# QRS_1_0.net
KiCad netlist of a schematic drawn in EAGLE
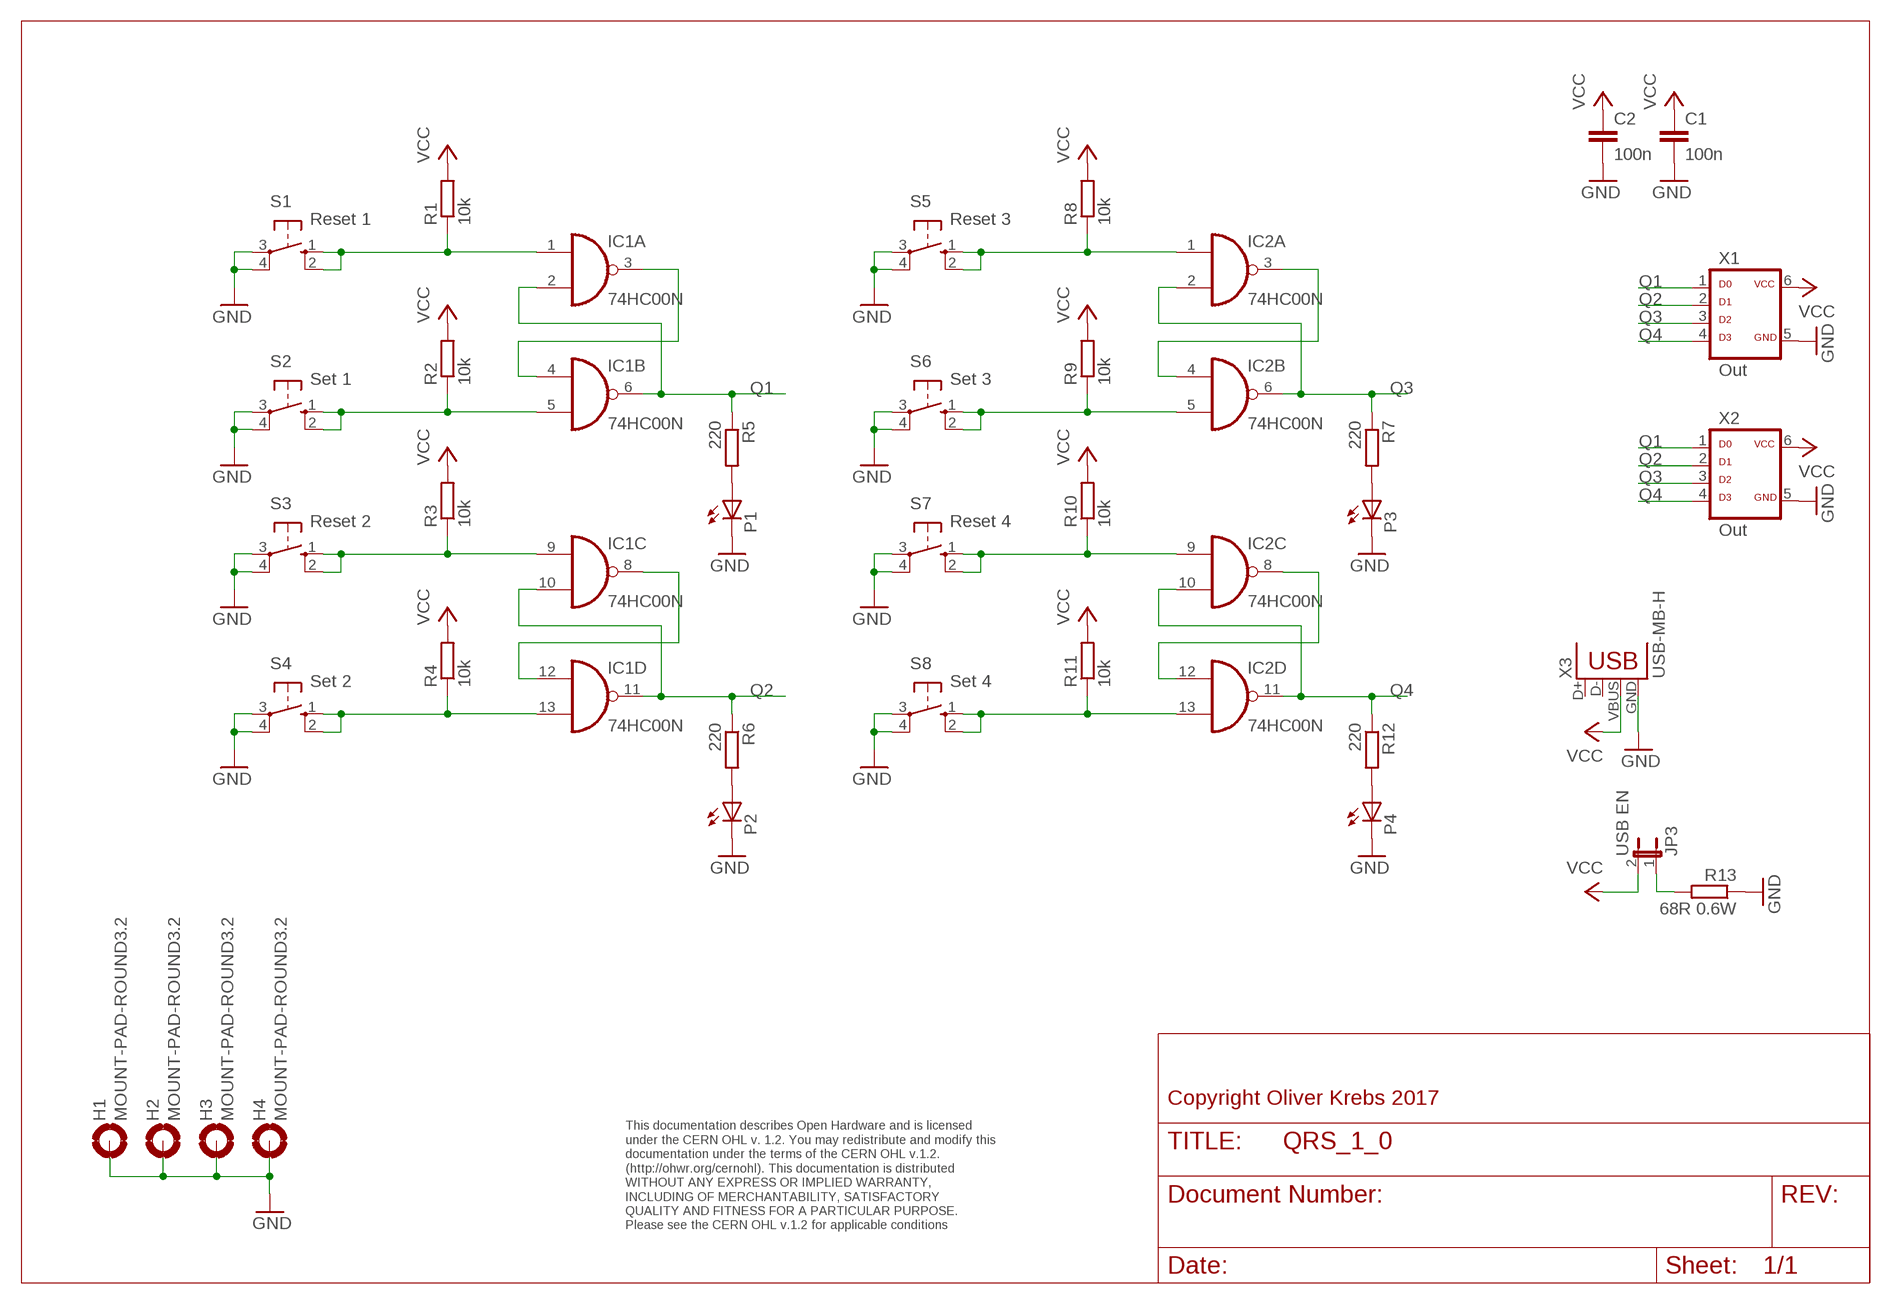
[diagram p0: schematic, sheet 1]

(export (version "E")
  (design (tool "Eeschema 10.0.6"))
  (components
    (comp (ref "C1")
      (value "100n")
      (footprint "eagle-import:C050-025X075")
      (libsource (lib "eagle-import") (part "C-EU050-025X075"))
    )
    (comp (ref "C2")
      (value "100n")
      (footprint "eagle-import:C050-025X075")
      (libsource (lib "eagle-import") (part "C-EU050-025X075"))
    )
    (comp (ref "H1")
      (value "MOUNT-PAD-ROUND3.2")
      (footprint "eagle-import:3,2-PAD")
      (libsource (lib "eagle-import") (part "MOUNT-PAD-ROUND3.2"))
    )
    (comp (ref "H2")
      (value "MOUNT-PAD-ROUND3.2")
      (footprint "eagle-import:3,2-PAD")
      (libsource (lib "eagle-import") (part "MOUNT-PAD-ROUND3.2"))
    )
    (comp (ref "H3")
      (value "MOUNT-PAD-ROUND3.2")
      (footprint "eagle-import:3,2-PAD")
      (libsource (lib "eagle-import") (part "MOUNT-PAD-ROUND3.2"))
    )
    (comp (ref "H4")
      (value "MOUNT-PAD-ROUND3.2")
      (footprint "eagle-import:3,2-PAD")
      (libsource (lib "eagle-import") (part "MOUNT-PAD-ROUND3.2"))
    )
    (comp (ref "IC1")
      (value "74HC00N")
      (footprint "eagle-import:DIL14")
      (libsource (lib "eagle-import") (part "7400NHC"))
    )
    (comp (ref "IC2")
      (value "74HC00N")
      (footprint "eagle-import:DIL14")
      (libsource (lib "eagle-import") (part "7400NHC"))
    )
    (comp (ref "JP3")
      (value "USB EN")
      (footprint "eagle-import:JP1")
      (libsource (lib "eagle-import") (part "JP1E"))
    )
    (comp (ref "P1")
      (value "LED3MM")
      (footprint "eagle-import:LED3MM")
      (libsource (lib "eagle-import") (part "LED3MM"))
    )
    (comp (ref "P2")
      (value "LED3MM")
      (footprint "eagle-import:LED3MM")
      (libsource (lib "eagle-import") (part "LED3MM"))
    )
    (comp (ref "P3")
      (value "LED3MM")
      (footprint "eagle-import:LED3MM")
      (libsource (lib "eagle-import") (part "LED3MM"))
    )
    (comp (ref "P4")
      (value "LED3MM")
      (footprint "eagle-import:LED3MM")
      (libsource (lib "eagle-import") (part "LED3MM"))
    )
    (comp (ref "R1")
      (value "10k")
      (footprint "eagle-import:0207_10")
      (libsource (lib "eagle-import") (part "R-EU_0207/10"))
    )
    (comp (ref "R2")
      (value "10k")
      (footprint "eagle-import:0207_10")
      (libsource (lib "eagle-import") (part "R-EU_0207/10"))
    )
    (comp (ref "R3")
      (value "10k")
      (footprint "eagle-import:0207_10")
      (libsource (lib "eagle-import") (part "R-EU_0207/10"))
    )
    (comp (ref "R4")
      (value "10k")
      (footprint "eagle-import:0207_10")
      (libsource (lib "eagle-import") (part "R-EU_0207/10"))
    )
    (comp (ref "R5")
      (value "220")
      (footprint "eagle-import:0207_10")
      (libsource (lib "eagle-import") (part "R-EU_0207/10"))
    )
    (comp (ref "R6")
      (value "220")
      (footprint "eagle-import:0207_10")
      (libsource (lib "eagle-import") (part "R-EU_0207/10"))
    )
    (comp (ref "R7")
      (value "220")
      (footprint "eagle-import:0207_10")
      (libsource (lib "eagle-import") (part "R-EU_0207/10"))
    )
    (comp (ref "R8")
      (value "10k")
      (footprint "eagle-import:0207_10")
      (libsource (lib "eagle-import") (part "R-EU_0207/10"))
    )
    (comp (ref "R9")
      (value "10k")
      (footprint "eagle-import:0207_10")
      (libsource (lib "eagle-import") (part "R-EU_0207/10"))
    )
    (comp (ref "R10")
      (value "10k")
      (footprint "eagle-import:0207_10")
      (libsource (lib "eagle-import") (part "R-EU_0207/10"))
    )
    (comp (ref "R11")
      (value "10k")
      (footprint "eagle-import:0207_10")
      (libsource (lib "eagle-import") (part "R-EU_0207/10"))
    )
    (comp (ref "R12")
      (value "220")
      (footprint "eagle-import:0207_10")
      (libsource (lib "eagle-import") (part "R-EU_0207/10"))
    )
    (comp (ref "R13")
      (value "68R 0.6W")
      (footprint "eagle-import:0207_10")
      (libsource (lib "eagle-import") (part "R-EU_0207/10"))
    )
    (comp (ref "S1")
      (value "Reset 1")
      (footprint "eagle-import:B3F-10XX")
      (fields (field (name "MPN") "B3F-1000"))
      (libsource (lib "eagle-import") (part "10-XX"))
    )
    (comp (ref "S2")
      (value "Set 1")
      (footprint "eagle-import:B3F-10XX")
      (fields (field (name "MPN") "B3F-1000"))
      (libsource (lib "eagle-import") (part "10-XX"))
    )
    (comp (ref "S3")
      (value "Reset 2")
      (footprint "eagle-import:B3F-10XX")
      (fields (field (name "MPN") "B3F-1000"))
      (libsource (lib "eagle-import") (part "10-XX"))
    )
    (comp (ref "S4")
      (value "Set 2")
      (footprint "eagle-import:B3F-10XX")
      (fields (field (name "MPN") "B3F-1000"))
      (libsource (lib "eagle-import") (part "10-XX"))
    )
    (comp (ref "S5")
      (value "Reset 3")
      (footprint "eagle-import:B3F-10XX")
      (fields (field (name "MPN") "B3F-1000"))
      (libsource (lib "eagle-import") (part "10-XX"))
    )
    (comp (ref "S6")
      (value "Set 3")
      (footprint "eagle-import:B3F-10XX")
      (fields (field (name "MPN") "B3F-1000"))
      (libsource (lib "eagle-import") (part "10-XX"))
    )
    (comp (ref "S7")
      (value "Reset 4")
      (footprint "eagle-import:B3F-10XX")
      (fields (field (name "MPN") "B3F-1000"))
      (libsource (lib "eagle-import") (part "10-XX"))
    )
    (comp (ref "S8")
      (value "Set 4")
      (footprint "eagle-import:B3F-10XX")
      (fields (field (name "MPN") "B3F-1000"))
      (libsource (lib "eagle-import") (part "10-XX"))
    )
    (comp (ref "X1")
      (value "Out")
      (footprint "eagle-import:ML-6")
      (libsource (lib "eagle-import") (part "ML6D"))
    )
    (comp (ref "X2")
      (value "Out")
      (footprint "eagle-import:ML-6")
      (libsource (lib "eagle-import") (part "ML6D"))
    )
    (comp (ref "X3")
      (value "USB-MB-H")
      (footprint "eagle-import:USB-MB-H")
      (libsource (lib "eagle-import") (part "USB-MB-H"))
    )
  )
  (nets
    (net (code "1") (name "/Q1") (class "Default")
      (node (ref "IC1") (pin "2") (pinfunction "I1_2") (pintype "input"))
      (node (ref "IC1") (pin "6") (pinfunction "O_6") (pintype "output"))
      (node (ref "R5") (pin "1") (pinfunction "1_1") (pintype "passive"))
      (node (ref "X1") (pin "1") (pinfunction "1_1") (pintype "passive"))
      (node (ref "X2") (pin "1") (pinfunction "1_1") (pintype "passive"))
    )
    (net (code "2") (name "/Q2") (class "Default")
      (node (ref "IC1") (pin "10") (pinfunction "I1_10") (pintype "input"))
      (node (ref "IC1") (pin "11") (pinfunction "O_11") (pintype "output"))
      (node (ref "R6") (pin "1") (pinfunction "1_1") (pintype "passive"))
      (node (ref "X1") (pin "2") (pinfunction "2_2") (pintype "passive"))
      (node (ref "X2") (pin "2") (pinfunction "2_2") (pintype "passive"))
    )
    (net (code "3") (name "/Q3") (class "Default")
      (node (ref "IC2") (pin "2") (pinfunction "I1_2") (pintype "input"))
      (node (ref "IC2") (pin "6") (pinfunction "O_6") (pintype "output"))
      (node (ref "R7") (pin "1") (pinfunction "1_1") (pintype "passive"))
      (node (ref "X1") (pin "3") (pinfunction "3_3") (pintype "passive"))
      (node (ref "X2") (pin "3") (pinfunction "3_3") (pintype "passive"))
    )
    (net (code "4") (name "/Q4") (class "Default")
      (node (ref "IC2") (pin "10") (pinfunction "I1_10") (pintype "input"))
      (node (ref "IC2") (pin "11") (pinfunction "O_11") (pintype "output"))
      (node (ref "R12") (pin "1") (pinfunction "1_1") (pintype "passive"))
      (node (ref "X1") (pin "4") (pinfunction "4_4") (pintype "passive"))
      (node (ref "X2") (pin "4") (pinfunction "4_4") (pintype "passive"))
    )
    (net (code "5") (name "GND") (class "Default")
      (node (ref "C1") (pin "2") (pinfunction "2_2") (pintype "passive"))
      (node (ref "C2") (pin "2") (pinfunction "2_2") (pintype "passive"))
      (node (ref "H1") (pin "B3,2") (pinfunction "MOUNT_B3,2") (pintype "passive"))
      (node (ref "H2") (pin "B3,2") (pinfunction "MOUNT_B3,2") (pintype "passive"))
      (node (ref "H3") (pin "B3,2") (pinfunction "MOUNT_B3,2") (pintype "passive"))
      (node (ref "H4") (pin "B3,2") (pinfunction "MOUNT_B3,2") (pintype "passive"))
      (node (ref "P1") (pin "K") (pinfunction "C_K") (pintype "passive"))
      (node (ref "P2") (pin "K") (pinfunction "C_K") (pintype "passive"))
      (node (ref "P3") (pin "K") (pinfunction "C_K") (pintype "passive"))
      (node (ref "P4") (pin "K") (pinfunction "C_K") (pintype "passive"))
      (node (ref "R13") (pin "1") (pinfunction "1_1") (pintype "passive"))
      (node (ref "S1") (pin "3") (pinfunction "P_3") (pintype "passive"))
      (node (ref "S1") (pin "4") (pinfunction "P1_4") (pintype "passive"))
      (node (ref "S2") (pin "3") (pinfunction "P_3") (pintype "passive"))
      (node (ref "S2") (pin "4") (pinfunction "P1_4") (pintype "passive"))
      (node (ref "S3") (pin "3") (pinfunction "P_3") (pintype "passive"))
      (node (ref "S3") (pin "4") (pinfunction "P1_4") (pintype "passive"))
      (node (ref "S4") (pin "3") (pinfunction "P_3") (pintype "passive"))
      (node (ref "S4") (pin "4") (pinfunction "P1_4") (pintype "passive"))
      (node (ref "S5") (pin "3") (pinfunction "P_3") (pintype "passive"))
      (node (ref "S5") (pin "4") (pinfunction "P1_4") (pintype "passive"))
      (node (ref "S6") (pin "3") (pinfunction "P_3") (pintype "passive"))
      (node (ref "S6") (pin "4") (pinfunction "P1_4") (pintype "passive"))
      (node (ref "S7") (pin "3") (pinfunction "P_3") (pintype "passive"))
      (node (ref "S7") (pin "4") (pinfunction "P1_4") (pintype "passive"))
      (node (ref "S8") (pin "3") (pinfunction "P_3") (pintype "passive"))
      (node (ref "S8") (pin "4") (pinfunction "P1_4") (pintype "passive"))
      (node (ref "X1") (pin "5") (pinfunction "5_5") (pintype "passive"))
      (node (ref "X2") (pin "5") (pinfunction "5_5") (pintype "passive"))
      (node (ref "X3") (pin "GND") (pinfunction "GND_GND") (pintype "bidirectional"))
    )
    (net (code "6") (name "Net-(IC1A-I0)") (class "Default")
      (node (ref "IC1") (pin "1") (pinfunction "I0_1") (pintype "input"))
      (node (ref "R1") (pin "1") (pinfunction "1_1") (pintype "passive"))
      (node (ref "S1") (pin "1") (pinfunction "S_1") (pintype "passive"))
      (node (ref "S1") (pin "2") (pinfunction "S1_2") (pintype "passive"))
    )
    (net (code "7") (name "Net-(IC1A-O)") (class "Default")
      (node (ref "IC1") (pin "3") (pinfunction "O_3") (pintype "output"))
      (node (ref "IC1") (pin "4") (pinfunction "I0_4") (pintype "input"))
    )
    (net (code "8") (name "Net-(IC1B-I1)") (class "Default")
      (node (ref "IC1") (pin "5") (pinfunction "I1_5") (pintype "input"))
      (node (ref "R2") (pin "1") (pinfunction "1_1") (pintype "passive"))
      (node (ref "S2") (pin "1") (pinfunction "S_1") (pintype "passive"))
      (node (ref "S2") (pin "2") (pinfunction "S1_2") (pintype "passive"))
    )
    (net (code "9") (name "Net-(IC1C-I0)") (class "Default")
      (node (ref "IC1") (pin "9") (pinfunction "I0_9") (pintype "input"))
      (node (ref "R3") (pin "1") (pinfunction "1_1") (pintype "passive"))
      (node (ref "S3") (pin "1") (pinfunction "S_1") (pintype "passive"))
      (node (ref "S3") (pin "2") (pinfunction "S1_2") (pintype "passive"))
    )
    (net (code "10") (name "Net-(IC1C-O)") (class "Default")
      (node (ref "IC1") (pin "12") (pinfunction "I0_12") (pintype "input"))
      (node (ref "IC1") (pin "8") (pinfunction "O_8") (pintype "output"))
    )
    (net (code "11") (name "Net-(IC1D-I1)") (class "Default")
      (node (ref "IC1") (pin "13") (pinfunction "I1_13") (pintype "input"))
      (node (ref "R4") (pin "1") (pinfunction "1_1") (pintype "passive"))
      (node (ref "S4") (pin "1") (pinfunction "S_1") (pintype "passive"))
      (node (ref "S4") (pin "2") (pinfunction "S1_2") (pintype "passive"))
    )
    (net (code "12") (name "Net-(IC2A-I0)") (class "Default")
      (node (ref "IC2") (pin "1") (pinfunction "I0_1") (pintype "input"))
      (node (ref "R8") (pin "1") (pinfunction "1_1") (pintype "passive"))
      (node (ref "S5") (pin "1") (pinfunction "S_1") (pintype "passive"))
      (node (ref "S5") (pin "2") (pinfunction "S1_2") (pintype "passive"))
    )
    (net (code "13") (name "Net-(IC2A-O)") (class "Default")
      (node (ref "IC2") (pin "3") (pinfunction "O_3") (pintype "output"))
      (node (ref "IC2") (pin "4") (pinfunction "I0_4") (pintype "input"))
    )
    (net (code "14") (name "Net-(IC2B-I1)") (class "Default")
      (node (ref "IC2") (pin "5") (pinfunction "I1_5") (pintype "input"))
      (node (ref "R9") (pin "1") (pinfunction "1_1") (pintype "passive"))
      (node (ref "S6") (pin "1") (pinfunction "S_1") (pintype "passive"))
      (node (ref "S6") (pin "2") (pinfunction "S1_2") (pintype "passive"))
    )
    (net (code "15") (name "Net-(IC2C-I0)") (class "Default")
      (node (ref "IC2") (pin "9") (pinfunction "I0_9") (pintype "input"))
      (node (ref "R10") (pin "1") (pinfunction "1_1") (pintype "passive"))
      (node (ref "S7") (pin "1") (pinfunction "S_1") (pintype "passive"))
      (node (ref "S7") (pin "2") (pinfunction "S1_2") (pintype "passive"))
    )
    (net (code "16") (name "Net-(IC2C-O)") (class "Default")
      (node (ref "IC2") (pin "12") (pinfunction "I0_12") (pintype "input"))
      (node (ref "IC2") (pin "8") (pinfunction "O_8") (pintype "output"))
    )
    (net (code "17") (name "Net-(IC2D-I1)") (class "Default")
      (node (ref "IC2") (pin "13") (pinfunction "I1_13") (pintype "input"))
      (node (ref "R11") (pin "1") (pinfunction "1_1") (pintype "passive"))
      (node (ref "S8") (pin "1") (pinfunction "S_1") (pintype "passive"))
      (node (ref "S8") (pin "2") (pinfunction "S1_2") (pintype "passive"))
    )
    (net (code "18") (name "Net-(JP3-Pad1)") (class "Default")
      (node (ref "JP3") (pin "1") (pinfunction "1_1") (pintype "passive"))
      (node (ref "R13") (pin "2") (pinfunction "2_2") (pintype "passive"))
    )
    (net (code "19") (name "Net-(P1-PadA)") (class "Default")
      (node (ref "P1") (pin "A") (pinfunction "A_A") (pintype "passive"))
      (node (ref "R5") (pin "2") (pinfunction "2_2") (pintype "passive"))
    )
    (net (code "20") (name "Net-(P2-PadA)") (class "Default")
      (node (ref "P2") (pin "A") (pinfunction "A_A") (pintype "passive"))
      (node (ref "R6") (pin "2") (pinfunction "2_2") (pintype "passive"))
    )
    (net (code "21") (name "Net-(P3-PadA)") (class "Default")
      (node (ref "P3") (pin "A") (pinfunction "A_A") (pintype "passive"))
      (node (ref "R7") (pin "2") (pinfunction "2_2") (pintype "passive"))
    )
    (net (code "22") (name "Net-(P4-PadA)") (class "Default")
      (node (ref "P4") (pin "A") (pinfunction "A_A") (pintype "passive"))
      (node (ref "R12") (pin "2") (pinfunction "2_2") (pintype "passive"))
    )
    (net (code "23") (name "VCC") (class "Default")
      (node (ref "C1") (pin "1") (pinfunction "1_1") (pintype "passive"))
      (node (ref "C2") (pin "1") (pinfunction "1_1") (pintype "passive"))
      (node (ref "JP3") (pin "2") (pinfunction "2_2") (pintype "passive"))
      (node (ref "R1") (pin "2") (pinfunction "2_2") (pintype "passive"))
      (node (ref "R10") (pin "2") (pinfunction "2_2") (pintype "passive"))
      (node (ref "R11") (pin "2") (pinfunction "2_2") (pintype "passive"))
      (node (ref "R2") (pin "2") (pinfunction "2_2") (pintype "passive"))
      (node (ref "R3") (pin "2") (pinfunction "2_2") (pintype "passive"))
      (node (ref "R4") (pin "2") (pinfunction "2_2") (pintype "passive"))
      (node (ref "R8") (pin "2") (pinfunction "2_2") (pintype "passive"))
      (node (ref "R9") (pin "2") (pinfunction "2_2") (pintype "passive"))
      (node (ref "X1") (pin "6") (pinfunction "6_6") (pintype "passive"))
      (node (ref "X2") (pin "6") (pinfunction "6_6") (pintype "passive"))
      (node (ref "X3") (pin "VBUS") (pinfunction "VBUS_VBUS") (pintype "bidirectional"))
    )
    (net (code "24") (name "unconnected-(X3-PadD+)") (class "Default")
      (node (ref "X3") (pin "D+") (pinfunction "D+_D+") (pintype "bidirectional"))
    )
    (net (code "25") (name "unconnected-(X3-PadD-)") (class "Default")
      (node (ref "X3") (pin "D-") (pinfunction "D-_D-") (pintype "bidirectional"))
    )
  )
)
